# power.net
KiCad netlist of a schematic drawn in Altium Designer
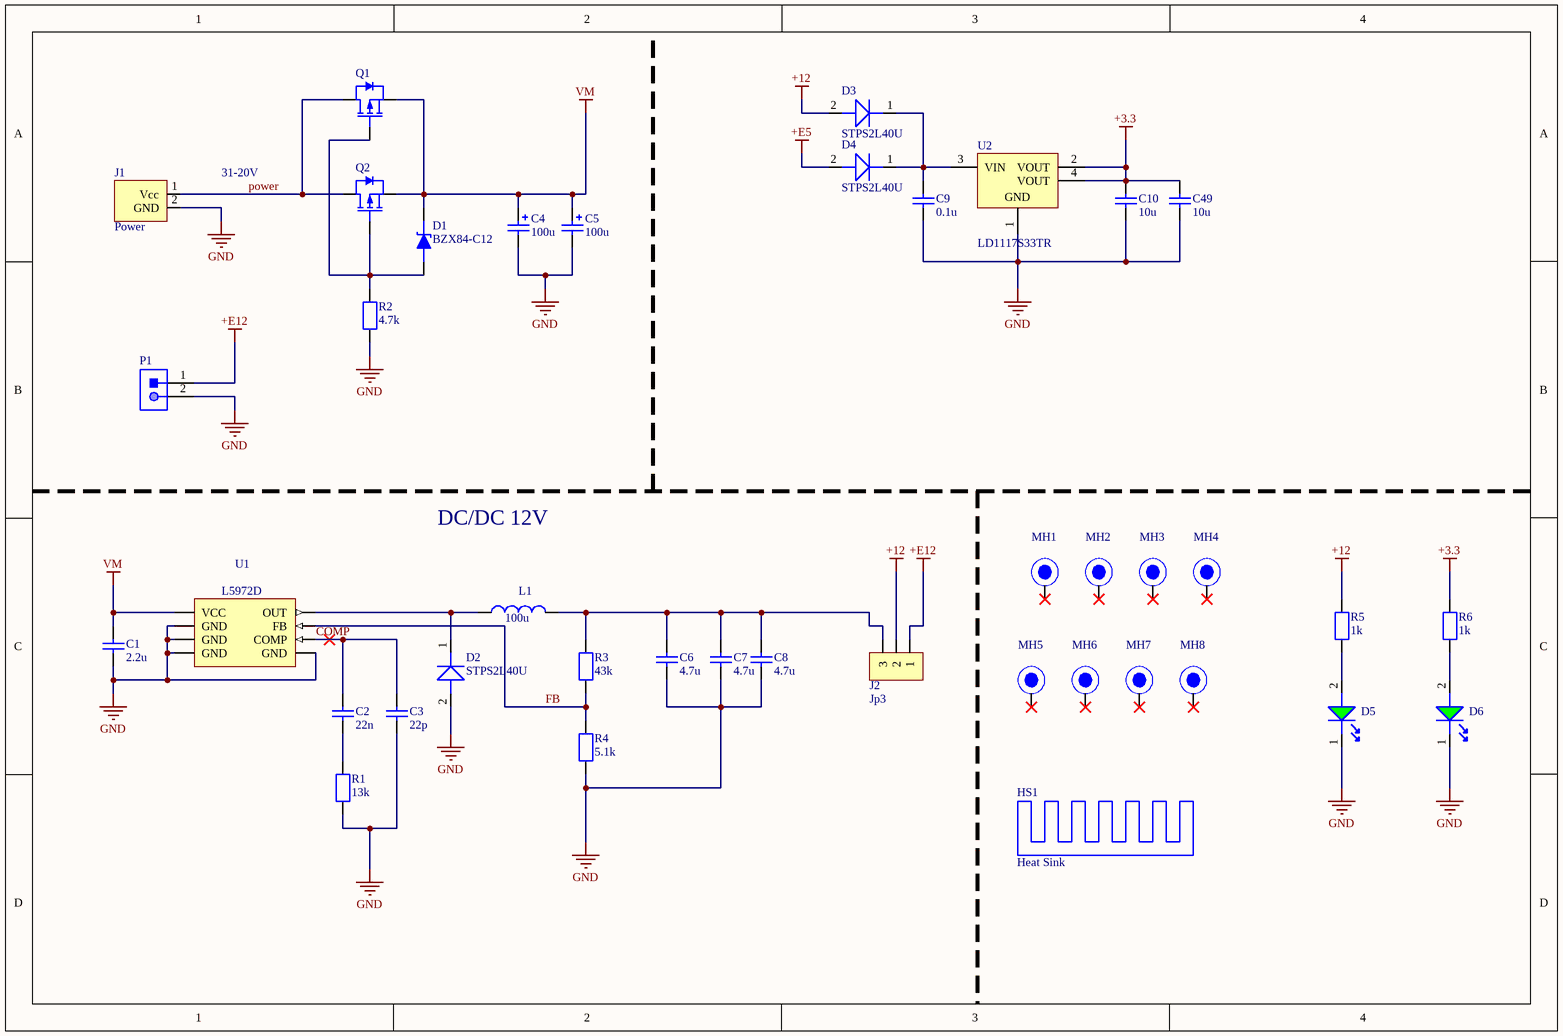
[diagram p0: power.SchDoc]

(export (version "E")
  (design (tool "Eeschema 10.0.6"))
  (components
    (comp (ref "C1")
      (value "2.2u")
      (footprint "CAP_1206")
      (description "GRM21BR71E225K, Конденсатор керамический smd 2.2мкФ X7R 25В 0805")
      (fields (field (name "Comment") "CAP"))
      (libsource (lib "Capacitors") (part "CAP"))
    )
    (comp (ref "C2")
      (value "22n")
      (footprint "CAPC2012X06N")
      (description "GRM31MR72A223K, Конденсатор керамический smd 0.022мкФ 100В X7R, 10%")
      (fields (field (name "Comment") "CAP"))
      (libsource (lib "Capacitors") (part "CAP"))
    )
    (comp (ref "C3")
      (value "22p")
      (footprint "CAPC2012X06N")
      (description "GRM21A5C2E220J, Конденсатор керамический smd 22пФ C0G 250B 5% 0805")
      (fields (field (name "Comment") "CAP"))
      (libsource (lib "Capacitors") (part "CAP"))
    )
    (comp (ref "C4")
      (value "100u")
      (footprint "B40940")
      (description "B40940A8107M000, 100 мкФ, 63 В,10х12.5, 20%")
      (fields (field (name "Comment") "Cap_Pos"))
      (libsource (lib "Capacitors") (part "Cap_Pos"))
    )
    (comp (ref "C5")
      (value "100u")
      (footprint "B40940")
      (description "B40940A8107M000, 100 мкФ, 63 В,10х12.5, 20%")
      (fields (field (name "Comment") "Cap_Pos"))
      (libsource (lib "Capacitors") (part "Cap_Pos"))
    )
    (comp (ref "C6")
      (value "4.7u")
      (footprint "CAP_1206")
      (description "GRM21BR61E475KA12L, Конденсатор керамический smd 4.7 мкФ X5R 10% 25В 0805")
      (fields (field (name "Comment") "CAP"))
      (libsource (lib "Capacitors") (part "CAP"))
    )
    (comp (ref "C7")
      (value "4.7u")
      (footprint "CAP_1206")
      (description "GRM21BR61E475KA12L, Конденсатор керамический smd 4.7 мкФ X5R 10% 25В 0805")
      (fields (field (name "Comment") "CAP"))
      (libsource (lib "Capacitors") (part "CAP"))
    )
    (comp (ref "C8")
      (value "4.7u")
      (footprint "CAP_1206")
      (description "GRM21BR61E475KA12L, Конденсатор керамический smd 4.7 мкФ X5R 10% 25В 0805")
      (fields (field (name "Comment") "CAP"))
      (libsource (lib "Capacitors") (part "CAP"))
    )
    (comp (ref "C9")
      (value "0.1u")
      (footprint "CAPC2012X06N")
      (description "Конденсатор керамический smd 0.01 мкФ NPO 50В 5%")
      (fields (field (name "Comment") "CAP"))
      (libsource (lib "Capacitors") (part "CAP"))
    )
    (comp (ref "C10")
      (value "10u")
      (footprint "CAPC2012X06N")
      (description "Capacitor SMD 0805 X7R 10uФ 25В 10%")
      (fields (field (name "Comment") "CAP"))
      (libsource (lib "Capacitors") (part "CAP"))
    )
    (comp (ref "C49")
      (value "10u")
      (footprint "CAPC2012X06N")
      (description "Capacitor SMD 0805 X7R 10uФ 25В 10%")
      (fields (field (name "Comment") "CAP"))
      (libsource (lib "Capacitors") (part "CAP"))
    )
    (comp (ref "D1")
      (value "BZX84-C12")
      (footprint "SOT23")
      (description "BZX84-C12,215, Стабилитрон 12В, 5%")
      (libsource (lib "Diods") (part "BZX84-C12"))
    )
    (comp (ref "D2")
      (value "STPS2L40U")
      (footprint "CAPM3216X18N")
      (description "STPS2L40U, Диод Шоттки 40В 2А")
      (libsource (lib "bldc_lib") (part "DIOD"))
    )
    (comp (ref "D3")
      (value "STPS2L40U")
      (footprint "CAPM3216X18N")
      (description "STPS2L40U, Диод Шоттки 40В 2А")
      (libsource (lib "bldc_lib") (part "DIOD"))
    )
    (comp (ref "D4")
      (value "STPS2L40U")
      (footprint "CAPM3216X18N")
      (description "STPS2L40U, Диод Шоттки 40В 2А")
      (libsource (lib "bldc_lib") (part "DIOD"))
    )
    (comp (ref "D5")
      (value "GREEN")
      (footprint "DIOC3216X06N")
      (description "TO-3216BC-BF, Светодиод синий SMD 3216")
      (libsource (lib "bldc_lib") (part "LED_G"))
    )
    (comp (ref "D6")
      (value "GREEN")
      (footprint "DIOC3216X06N")
      (description "TO-3216BC-BF, Светодиод синий SMD 3216")
      (libsource (lib "bldc_lib") (part "LED_G"))
    )
    (comp (ref "HS1")
      (value "Heat Sink")
      (footprint "Heat Sink")
      (description "HS 145-100, Радиатор 100х100х26 мм")
      (libsource (lib "bldc_lib") (part "Heat Sink"))
    )
    (comp (ref "J1")
      (value "Power")
      (footprint "Power Connector")
      (libsource (lib "bldc_lib") (part "Power"))
    )
    (comp (ref "J2")
      (value "Jp3")
      (footprint "HEADER 1x3 2.54mm")
      (description "PLS-3 (DS1021-1x3), Вилка штыревая 2.54мм 1x3pin")
      (libsource (lib "bldc_lib") (part "Jumper3"))
    )
    (comp (ref "L1")
      (value "100u")
      (footprint "HE1040")
      (description "HE1040 101M2B 100мкГн ± 25%")
      (fields (field (name "Comment") "HE1040"))
      (libsource (lib "bldc_lib") (part "L"))
    )
    (comp (ref "MH1") (value "MH") (footprint "MH") (libsource (lib "bldc_lib") (part "MH")))
    (comp (ref "MH2") (value "MH") (footprint "MH") (libsource (lib "bldc_lib") (part "MH")))
    (comp (ref "MH3") (value "MH") (footprint "MH") (libsource (lib "bldc_lib") (part "MH")))
    (comp (ref "MH4") (value "MH") (footprint "MH") (libsource (lib "bldc_lib") (part "MH")))
    (comp (ref "MH5") (value "MH") (footprint "MH") (libsource (lib "bldc_lib") (part "MH")))
    (comp (ref "MH6") (value "MH") (footprint "MH") (libsource (lib "bldc_lib") (part "MH")))
    (comp (ref "MH7") (value "MH") (footprint "MH") (libsource (lib "bldc_lib") (part "MH")))
    (comp (ref "MH8") (value "MH") (footprint "MH") (libsource (lib "bldc_lib") (part "MH")))
    (comp (ref "P1")
      (value "B2P-VH(LF)(SN)")
      (footprint "JST-B2P-VH(LF)(SN)_V")
      (fields (field (name "MANUFACTURER") "JST"))
      (libsource (lib "Discover Tour") (part "CN-1P-M-R2"))
    )
    (comp (ref "Q1")
      (value "IRF4905STRLPBF")
      (footprint "FP-PG-TO263-3-MFG")
      (description "IRF4905STRLPBF, Транзистор HEXFET, P-канал, 55В, 74А")
      (libsource (lib "Transistors") (part "PMOS"))
    )
    (comp (ref "Q2")
      (value "IRF4905STRLPBF")
      (footprint "FP-PG-TO263-3-MFG")
      (description "IRF4905STRLPBF, Транзистор HEXFET, P-канал, 55В, 74А")
      (libsource (lib "Transistors") (part "PMOS"))
    )
    (comp (ref "R1")
      (value "13k")
      (footprint "RESC2012X06N")
      (description "0.125Вт 0805 13 кОм, 1%")
      (fields (field (name "Comment") "Resistor"))
      (libsource (lib "Resistor") (part "Resistor"))
    )
    (comp (ref "R2")
      (value "4.7k")
      (footprint "RESC2012X06N")
      (description "0.125Вт 0805 4.7 кОм, 1%")
      (fields (field (name "Comment") "Resistor"))
      (libsource (lib "Resistor") (part "Resistor"))
    )
    (comp (ref "R3")
      (value "43k")
      (footprint "RESC2012X06N")
      (description "0.125Вт 0805 43 кОм, 1%")
      (fields (field (name "Comment") "Resistor"))
      (libsource (lib "Resistor") (part "Resistor"))
    )
    (comp (ref "R4")
      (value "5.1k")
      (footprint "RESC2012X06N")
      (description "0.125Вт 0805 5.1 кОм, 1%")
      (fields (field (name "Comment") "Resistor"))
      (libsource (lib "Resistor") (part "Resistor"))
    )
    (comp (ref "R5")
      (value "1k")
      (footprint "RESC2012X06N")
      (description "0.125Вт 0805 1 кОм, 1%")
      (fields (field (name "Comment") "Resistor"))
      (libsource (lib "Resistor") (part "Resistor"))
    )
    (comp (ref "R6")
      (value "1k")
      (footprint "RESC2012X06N")
      (description "0.125Вт 0805 1 кОм, 1%")
      (fields (field (name "Comment") "Resistor"))
      (libsource (lib "Resistor") (part "Resistor"))
    )
    (comp (ref "U1")
      (value "L5972D")
      (footprint "SO-8")
      (description "Buck Switching Regulator IC Positive Adjustable 1.235V 1 Output 2A 8-SOIC (0.154\", 3.90mm Width)")
      (libsource (lib "bldc_lib") (part "L5972D"))
    )
    (comp (ref "U2")
      (value "LD1117S33TR")
      (footprint "STM-SOT-223_M")
      (fields (field (name "POWER") "12W") (field (name "MANUFACTURER") "STMicroelectronics"))
      (libsource (lib "Discover Tour") (part "STM-LD1117-SOT223-4"))
    )
  )
  (nets
    (net (code "1") (name "+3.3") (class "Default")
      (node (ref "C10") (pin "1") (pinfunction "2_1") (pintype "passive"))
      (node (ref "C49") (pin "1") (pinfunction "2_1") (pintype "passive"))
      (node (ref "R6") (pin "2") (pinfunction "*_2") (pintype "passive"))
      (node (ref "U2") (pin "2") (pinfunction "VOUT_2") (pintype "power_in"))
      (node (ref "U2") (pin "4") (pinfunction "VOUT_4") (pintype "power_in"))
    )
    (net (code "2") (name "+12") (class "Default")
      (node (ref "D3") (pin "2") (pinfunction "A_2") (pintype "passive"))
      (node (ref "J2") (pin "2") (pinfunction "2_2") (pintype "passive"))
      (node (ref "R5") (pin "2") (pinfunction "*_2") (pintype "passive"))
    )
    (net (code "3") (name "+E5") (class "Default")
      (node (ref "D4") (pin "2") (pinfunction "A_2") (pintype "passive"))
    )
    (net (code "4") (name "+E12") (class "Default")
      (node (ref "J2") (pin "1") (pinfunction "1_1") (pintype "passive"))
      (node (ref "P1") (pin "1") (pinfunction "1_1") (pintype "passive"))
    )
    (net (code "5") (name "/COMP") (class "Default")
      (node (ref "C2") (pin "1") (pinfunction "2_1") (pintype "passive"))
      (node (ref "C3") (pin "1") (pinfunction "2_1") (pintype "passive"))
      (node (ref "U1") (pin "4") (pinfunction "COMP_4") (pintype "input"))
    )
    (net (code "6") (name "/FB") (class "Default")
      (node (ref "R3") (pin "1") (pinfunction "*_1") (pintype "passive"))
      (node (ref "R4") (pin "2") (pinfunction "*_2") (pintype "passive"))
      (node (ref "U1") (pin "5") (pinfunction "FB_5") (pintype "input"))
    )
    (net (code "7") (name "/power") (class "Default")
      (node (ref "J1") (pin "1") (pinfunction "Vcc_1") (pintype "power_in"))
      (node (ref "Q1") (pin "D") (pinfunction "D_D") (pintype "passive"))
      (node (ref "Q2") (pin "D") (pinfunction "D_D") (pintype "passive"))
    )
    (net (code "8") (name "GND") (class "Default")
      (node (ref "C1") (pin "2") (pinfunction "1_2") (pintype "passive"))
      (node (ref "C10") (pin "2") (pinfunction "1_2") (pintype "passive"))
      (node (ref "C3") (pin "2") (pinfunction "1_2") (pintype "passive"))
      (node (ref "C4") (pin "2") (pinfunction "2_2") (pintype "passive"))
      (node (ref "C49") (pin "2") (pinfunction "1_2") (pintype "passive"))
      (node (ref "C5") (pin "2") (pinfunction "2_2") (pintype "passive"))
      (node (ref "C6") (pin "2") (pinfunction "1_2") (pintype "passive"))
      (node (ref "C7") (pin "2") (pinfunction "1_2") (pintype "passive"))
      (node (ref "C8") (pin "2") (pinfunction "1_2") (pintype "passive"))
      (node (ref "C9") (pin "2") (pinfunction "1_2") (pintype "passive"))
      (node (ref "D2") (pin "2") (pinfunction "A_2") (pintype "passive"))
      (node (ref "D5") (pin "1") (pinfunction "1_1") (pintype "passive"))
      (node (ref "D6") (pin "1") (pinfunction "1_1") (pintype "passive"))
      (node (ref "J1") (pin "2") (pinfunction "GND_2") (pintype "power_in"))
      (node (ref "P1") (pin "2") (pinfunction "2_2") (pintype "passive"))
      (node (ref "R1") (pin "1") (pinfunction "*_1") (pintype "passive"))
      (node (ref "R2") (pin "1") (pinfunction "*_1") (pintype "passive"))
      (node (ref "R4") (pin "1") (pinfunction "*_1") (pintype "passive"))
      (node (ref "U1") (pin "2") (pinfunction "GND_2") (pintype "power_in"))
      (node (ref "U1") (pin "3") (pinfunction "GND_3") (pintype "power_in"))
      (node (ref "U1") (pin "6") (pinfunction "GND_6") (pintype "power_in"))
      (node (ref "U1") (pin "7") (pinfunction "GND_7") (pintype "power_in"))
      (node (ref "U2") (pin "1") (pinfunction "GND_1") (pintype "power_in"))
    )
    (net (code "9") (name "Net-(C2-1)") (class "Default")
      (node (ref "C2") (pin "2") (pinfunction "1_2") (pintype "passive"))
      (node (ref "R1") (pin "2") (pinfunction "*_2") (pintype "passive"))
    )
    (net (code "10") (name "Net-(C6-2)") (class "Default")
      (node (ref "C6") (pin "1") (pinfunction "2_1") (pintype "passive"))
      (node (ref "C7") (pin "1") (pinfunction "2_1") (pintype "passive"))
      (node (ref "C8") (pin "1") (pinfunction "2_1") (pintype "passive"))
      (node (ref "J2") (pin "3") (pinfunction "3_3") (pintype "passive"))
      (node (ref "L1") (pin "2") (pintype "passive"))
      (node (ref "R3") (pin "2") (pinfunction "*_2") (pintype "passive"))
    )
    (net (code "11") (name "Net-(C9-2)") (class "Default")
      (node (ref "C9") (pin "1") (pinfunction "2_1") (pintype "passive"))
      (node (ref "D3") (pin "1") (pinfunction "K_1") (pintype "passive"))
      (node (ref "D4") (pin "1") (pinfunction "K_1") (pintype "passive"))
      (node (ref "U2") (pin "3") (pinfunction "VIN_3") (pintype "power_in"))
    )
    (net (code "12") (name "Net-(D1-2)") (class "Default")
      (node (ref "D1") (pin "1") (pinfunction "2_1") (pintype "passive"))
      (node (ref "Q1") (pin "G") (pinfunction "G_G") (pintype "passive"))
      (node (ref "Q2") (pin "G") (pinfunction "G_G") (pintype "passive"))
      (node (ref "R2") (pin "2") (pinfunction "*_2") (pintype "passive"))
    )
    (net (code "13") (name "Net-(D2-K)") (class "Default")
      (node (ref "D2") (pin "1") (pinfunction "K_1") (pintype "passive"))
      (node (ref "L1") (pin "1") (pintype "passive"))
      (node (ref "U1") (pin "1") (pinfunction "OUT_1") (pintype "output"))
    )
    (net (code "14") (name "Net-(D5-Pad2)") (class "Default")
      (node (ref "D5") (pin "2") (pinfunction "2_2") (pintype "passive"))
      (node (ref "R5") (pin "1") (pinfunction "*_1") (pintype "passive"))
    )
    (net (code "15") (name "Net-(D6-Pad2)") (class "Default")
      (node (ref "D6") (pin "2") (pinfunction "2_2") (pintype "passive"))
      (node (ref "R6") (pin "1") (pinfunction "*_1") (pintype "passive"))
    )
    (net (code "16") (name "VM") (class "Default")
      (node (ref "C1") (pin "1") (pinfunction "2_1") (pintype "passive"))
      (node (ref "C4") (pin "1") (pinfunction "1_1") (pintype "passive"))
      (node (ref "C5") (pin "1") (pinfunction "1_1") (pintype "passive"))
      (node (ref "D1") (pin "3") (pinfunction "3_3") (pintype "passive"))
      (node (ref "Q1") (pin "S") (pinfunction "S_S") (pintype "passive"))
      (node (ref "Q2") (pin "S") (pinfunction "S_S") (pintype "passive"))
      (node (ref "U1") (pin "8") (pinfunction "VCC_8") (pintype "power_in"))
    )
    (net (code "17") (name "unconnected-(MH1-Pad1)") (class "Default")
      (node (ref "MH1") (pin "1") (pinfunction "1_1") (pintype "passive+no_connect"))
    )
    (net (code "18") (name "unconnected-(MH2-Pad1)") (class "Default")
      (node (ref "MH2") (pin "1") (pinfunction "1_1") (pintype "passive+no_connect"))
    )
    (net (code "19") (name "unconnected-(MH3-Pad1)") (class "Default")
      (node (ref "MH3") (pin "1") (pinfunction "1_1") (pintype "passive+no_connect"))
    )
    (net (code "20") (name "unconnected-(MH4-Pad1)") (class "Default")
      (node (ref "MH4") (pin "1") (pinfunction "1_1") (pintype "passive+no_connect"))
    )
    (net (code "21") (name "unconnected-(MH5-Pad1)") (class "Default")
      (node (ref "MH5") (pin "1") (pinfunction "1_1") (pintype "passive+no_connect"))
    )
    (net (code "22") (name "unconnected-(MH6-Pad1)") (class "Default")
      (node (ref "MH6") (pin "1") (pinfunction "1_1") (pintype "passive+no_connect"))
    )
    (net (code "23") (name "unconnected-(MH7-Pad1)") (class "Default")
      (node (ref "MH7") (pin "1") (pinfunction "1_1") (pintype "passive+no_connect"))
    )
    (net (code "24") (name "unconnected-(MH8-Pad1)") (class "Default")
      (node (ref "MH8") (pin "1") (pinfunction "1_1") (pintype "passive+no_connect"))
    )
  )
)
